# Rat_Clone_V1_0.net
KiCad netlist of a schematic drawn in EAGLE
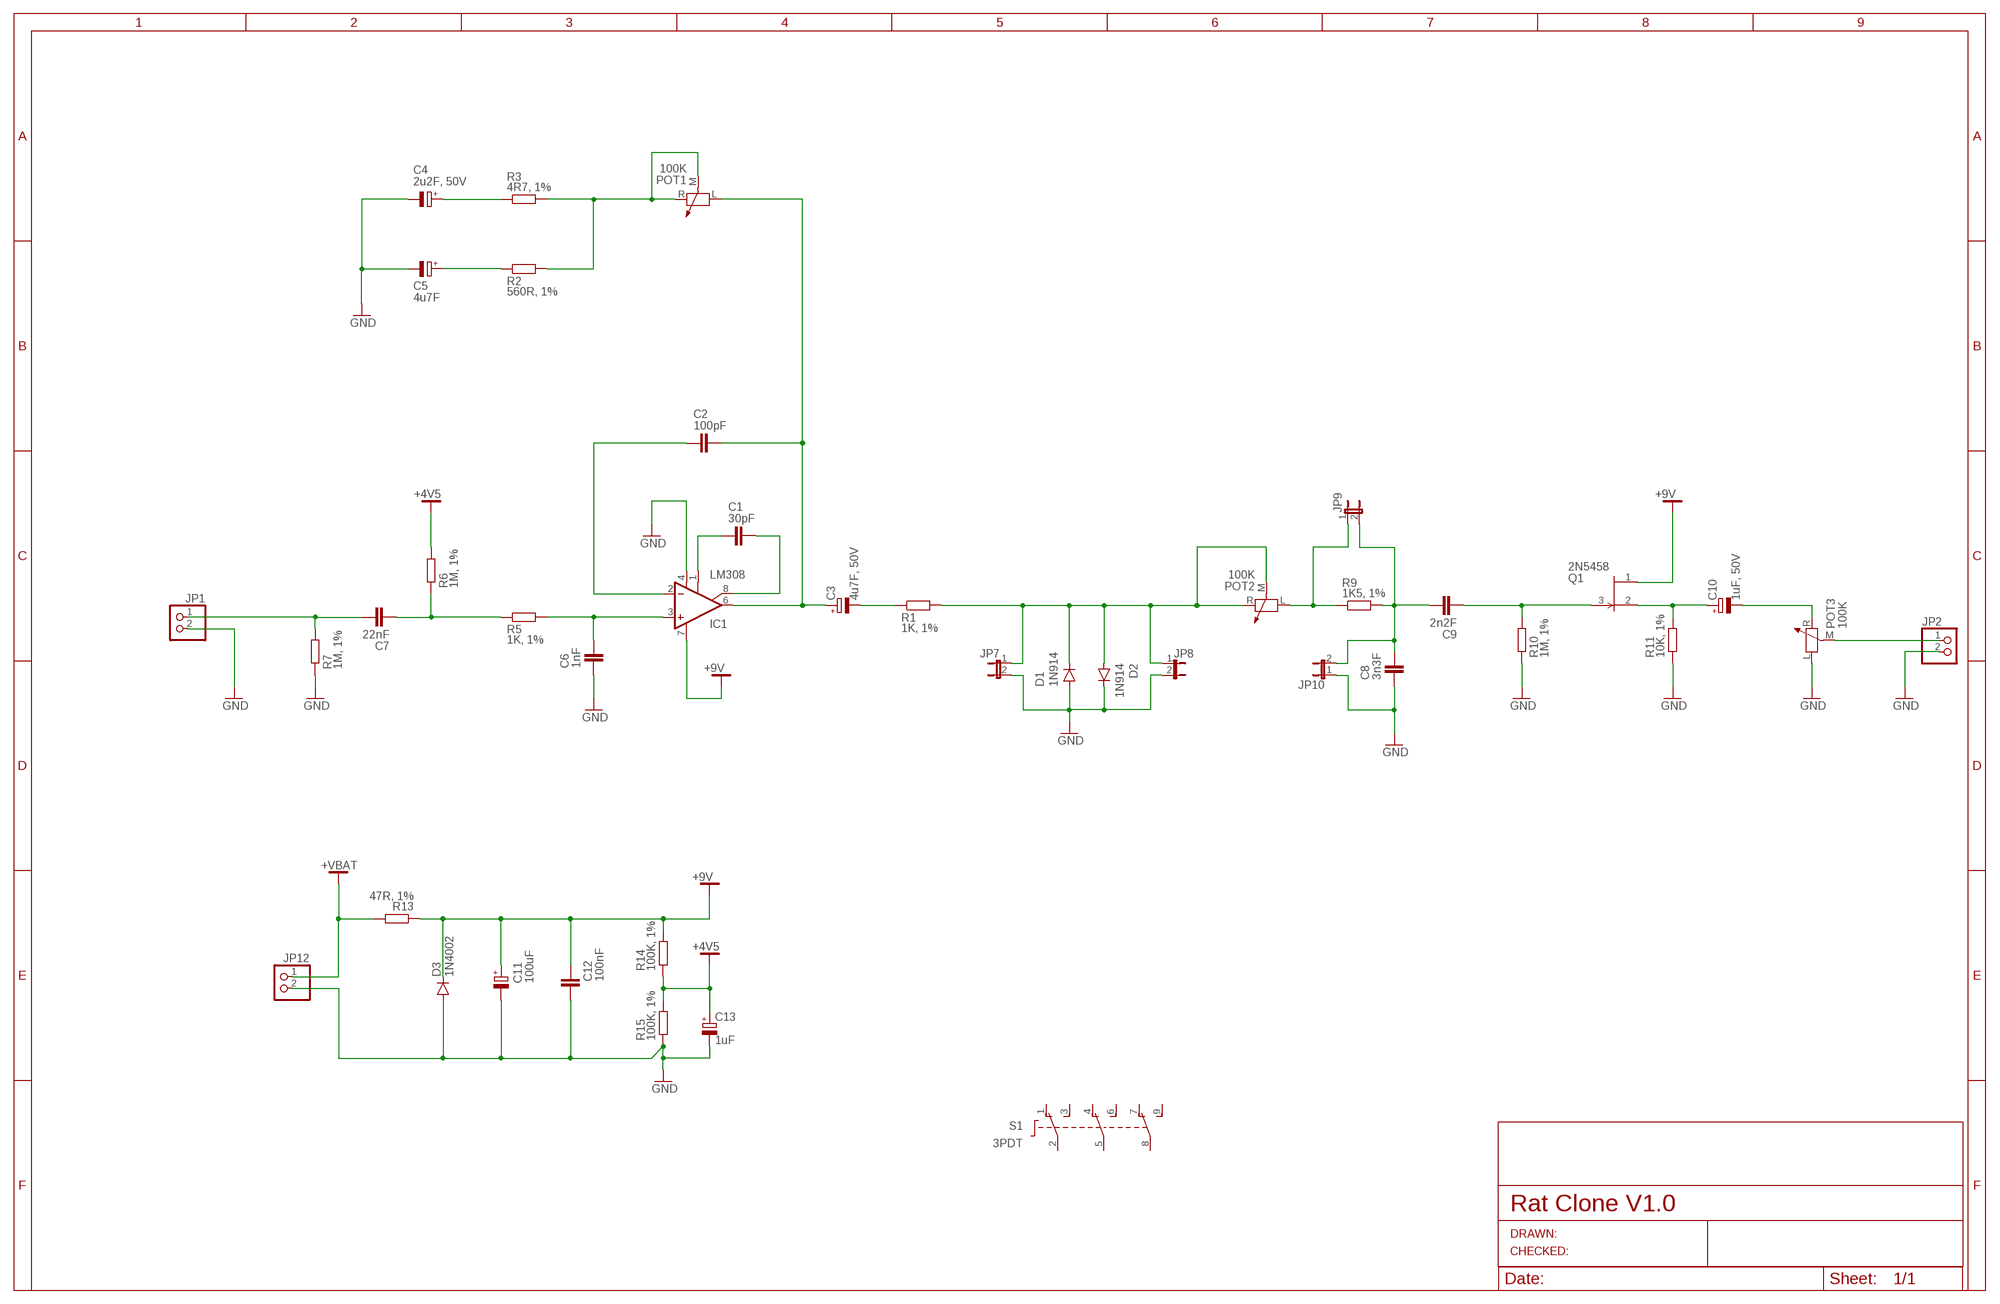
[diagram p0: schematic, sheet 1]

(export (version "E")
  (design (tool "Eeschema 10.0.6"))
  (components
    (comp (ref "C1")
      (value "30pF")
      (footprint "eagle-import:C025-025X050")
      (fields (field (name "MF") "KEMET ") (field (name "MPN") "C315C300J3G5TA"))
      (libsource (lib "eagle-import") (part "C-EU025-025X050"))
    )
    (comp (ref "C2")
      (value "100pF")
      (footprint "eagle-import:C025-025X050")
      (fields (field (name "MF") "Vishay / BC Components ") (field (name "MPN") "K101J15C0GF5TL2"))
      (libsource (lib "eagle-import") (part "C-EU025-025X050"))
    )
    (comp (ref "C3")
      (value "4u7F, 50V")
      (footprint "eagle-import:E2,5-6")
      (fields (field (name "MF") "MULTICOMP PRO") (field (name "MPN") "MCGPR50V475M5X11"))
      (libsource (lib "eagle-import") (part "CPOL-EUE2.5-6"))
    )
    (comp (ref "C4")
      (value "2u2F, 50V")
      (footprint "eagle-import:E2,5-6")
      (fields (field (name "MF") "MULTICOMP PRO") (field (name "MPN") "MCMR50V225M4X7"))
      (libsource (lib "eagle-import") (part "CPOL-EUE2.5-6"))
    )
    (comp (ref "C5")
      (value "4u7F")
      (footprint "eagle-import:E2,5-6")
      (fields (field (name "MF") "MULTICOMP PRO") (field (name "MPN") "MCMR50V475M4X7"))
      (libsource (lib "eagle-import") (part "CPOL-EUE2.5-6"))
    )
    (comp (ref "C6")
      (value "1nF")
      (footprint "eagle-import:C025-025X050")
      (fields (field (name "MF") "KEMET") (field (name "MPN") "R82EC1100DQ50J"))
      (libsource (lib "eagle-import") (part "C-EU025-025X050"))
    )
    (comp (ref "C7")
      (value "22nF")
      (footprint "eagle-import:C050-025X075")
      (fields (field (name "MF") "KEMET") (field (name "MPN") "R82EC2220DQ50JB"))
      (libsource (lib "eagle-import") (part "C-EU050-025X075"))
    )
    (comp (ref "C8")
      (value "3n3F")
      (footprint "eagle-import:C025-025X050")
      (fields (field (name "MF") "kemet") (field (name "MPN") "R82EC1330DQ50JB"))
      (libsource (lib "eagle-import") (part "C-EU025-025X050"))
    )
    (comp (ref "C9")
      (value "2n2F")
      (footprint "eagle-import:C025-025X050")
      (fields (field (name "MF") "Faratronic") (field (name "MPN") "C242A222J20C450"))
      (libsource (lib "eagle-import") (part "C-EU025-025X050"))
    )
    (comp (ref "C10")
      (value "1uF, 50V")
      (footprint "eagle-import:E2,5-6")
      (fields (field (name "MF") "MULTICOMP PRO") (field (name "MPN") "MCGPR50V105M5X11"))
      (libsource (lib "eagle-import") (part "CPOL-EUE2.5-6"))
    )
    (comp (ref "C11")
      (value "100uF")
      (footprint "eagle-import:E2,5-5")
      (fields (field (name "MF") "KEMET ") (field (name "MPN") "ESK107M016AC3AA "))
      (libsource (lib "eagle-import") (part "CPOL-EUE2.5-5"))
    )
    (comp (ref "C12")
      (value "100nF")
      (footprint "eagle-import:C025-025X050")
      (fields (field (name "MF") "KEMET") (field (name "MPN") "R82EC3100DQ70JB"))
      (libsource (lib "eagle-import") (part "C-EU025-025X050"))
    )
    (comp (ref "C13")
      (value "1uF")
      (footprint "eagle-import:E2,5-6")
      (fields (field (name "MF") "MULTICOMP PRO") (field (name "MPN") "MCGPR50V105M5X11"))
      (libsource (lib "eagle-import") (part "CPOL-EUE2.5-6"))
    )
    (comp (ref "D1")
      (value "1N914")
      (footprint "eagle-import:DO35-10")
      (fields (field (name "MF") "Fairchild Semiconductor") (field (name "MPN") "1N914"))
      (libsource (lib "eagle-import") (part "1N4148DO35-10"))
    )
    (comp (ref "D2")
      (value "1N914")
      (footprint "eagle-import:DO35-10")
      (fields (field (name "MF") "Fairchild Semiconductor") (field (name "MPN") "1N914"))
      (libsource (lib "eagle-import") (part "1N4148DO35-10"))
    )
    (comp (ref "D3")
      (value "1N4002")
      (footprint "eagle-import:DO41-10")
      (fields (field (name "MF") "onsemi ") (field (name "MPN") "1N4002G "))
      (libsource (lib "eagle-import") (part "1N4004"))
    )
    (comp (ref "IC1")
      (value "LM308")
      (footprint "eagle-import:DIL08")
      (libsource (lib "eagle-import") (part "LM308N"))
    )
    (comp (ref "JP1")
      (value "PINHD-1X2")
      (footprint "eagle-import:1X02")
      (fields (field (name "MF") "TruConnect") (field (name "MPN") "20-0134"))
      (libsource (lib "eagle-import") (part "PINHD-1X2"))
    )
    (comp (ref "JP2")
      (value "PINHD-1X2")
      (footprint "eagle-import:1X02")
      (fields (field (name "MF") "TruConnect") (field (name "MPN") "20-0134"))
      (libsource (lib "eagle-import") (part "PINHD-1X2"))
    )
    (comp (ref "JP7")
      (value "JP1E")
      (footprint "eagle-import:JP1")
      (libsource (lib "eagle-import") (part "JP1E"))
    )
    (comp (ref "JP8")
      (value "JP1E")
      (footprint "eagle-import:JP1")
      (libsource (lib "eagle-import") (part "JP1E"))
    )
    (comp (ref "JP9")
      (value "JP1E")
      (footprint "eagle-import:JP1")
      (libsource (lib "eagle-import") (part "JP1E"))
    )
    (comp (ref "JP10")
      (value "JP1E")
      (footprint "eagle-import:JP1")
      (libsource (lib "eagle-import") (part "JP1E"))
    )
    (comp (ref "JP12")
      (value "PINHD-1X2")
      (footprint "eagle-import:1X02")
      (fields (field (name "MF") "TruConnect") (field (name "MPN") "20-0134"))
      (libsource (lib "eagle-import") (part "PINHD-1X2"))
    )
    (comp (ref "POT1")
      (value "100K")
      (footprint "eagle-import:MA03-1")
      (libsource (lib "eagle-import") (part "WIRED_POT"))
    )
    (comp (ref "POT2")
      (value "100K")
      (footprint "eagle-import:MA03-1")
      (libsource (lib "eagle-import") (part "WIRED_POT"))
    )
    (comp (ref "POT3")
      (value "100K")
      (footprint "eagle-import:MA03-1")
      (libsource (lib "eagle-import") (part "WIRED_POT"))
    )
    (comp (ref "Q1")
      (value "2N5458")
      (footprint "eagle-import:TO92-")
      (fields (field (name "MF") "Central Semiconductor ") (field (name "MPN") "2N5458 PBFREE"))
      (libsource (lib "eagle-import") (part "2N5458"))
    )
    (comp (ref "R1")
      (value "1K, 1%")
      (footprint "eagle-import:0207_7")
      (fields (field (name "MF") "Royal Ohm") (field (name "MPN") "MF0W4FF1001KIT"))
      (libsource (lib "eagle-import") (part "R-EU_0207/7"))
    )
    (comp (ref "R2")
      (value "560R, 1%")
      (footprint "eagle-import:0207_7")
      (fields (field (name "MF") "Royal Ohm") (field (name "MPN") "MFF04FF5600KIT"))
      (libsource (lib "eagle-import") (part "R-EU_0207/7"))
    )
    (comp (ref "R3")
      (value "4R7, 1%")
      (footprint "eagle-import:0207_7")
      (fields (field (name "MF") "Royal Ohm") (field (name "MPN") "MF0W4FF470KKIT"))
      (libsource (lib "eagle-import") (part "R-EU_0207/7"))
    )
    (comp (ref "R5")
      (value "1K, 1%")
      (footprint "eagle-import:0207_7")
      (fields (field (name "MF") "Royal Ohm") (field (name "MPN") "MF0W4FF1001KIT"))
      (libsource (lib "eagle-import") (part "R-EU_0207/7"))
    )
    (comp (ref "R6")
      (value "1M, 1%")
      (footprint "eagle-import:0207_7")
      (fields (field (name "MF") "Royal Ohm") (field (name "MPN") "MF0W4FF1004KIT"))
      (libsource (lib "eagle-import") (part "R-EU_0207/7"))
    )
    (comp (ref "R7")
      (value "1M, 1%")
      (footprint "eagle-import:0207_7")
      (fields (field (name "MF") "Royal Ohm") (field (name "MPN") "MF0W4FF1004KIT"))
      (libsource (lib "eagle-import") (part "R-EU_0207/7"))
    )
    (comp (ref "R9")
      (value "1K5, 1%")
      (footprint "eagle-import:0207_7")
      (fields (field (name "MF") "Royal Ohm") (field (name "MPN") "MF0W4FF1501KIT"))
      (libsource (lib "eagle-import") (part "R-EU_0207/7"))
    )
    (comp (ref "R10")
      (value "1M, 1%")
      (footprint "eagle-import:0207_7")
      (fields (field (name "MF") "Royal Ohm") (field (name "MPN") "MF0W4FF1004KIT"))
      (libsource (lib "eagle-import") (part "R-EU_0207/7"))
    )
    (comp (ref "R11")
      (value "10K, 1%")
      (footprint "eagle-import:0207_7")
      (fields (field (name "MF") "Royal Ohm") (field (name "MPN") "MF0W4FF1002KIT"))
      (libsource (lib "eagle-import") (part "R-EU_0207/7"))
    )
    (comp (ref "R13")
      (value "47R, 1%")
      (footprint "eagle-import:0207_7")
      (fields (field (name "MF") "Royal Ohm") (field (name "MPN") "MF006FF470JKIT"))
      (libsource (lib "eagle-import") (part "R-EU_0207/7"))
    )
    (comp (ref "R14")
      (value "100K, 1%")
      (footprint "eagle-import:0207_7")
      (fields (field (name "MF") "Royal Ohm") (field (name "MPN") "MF0W4FF1003KIT"))
      (libsource (lib "eagle-import") (part "R-EU_0207/7"))
    )
    (comp (ref "R15")
      (value "100K, 1%")
      (footprint "eagle-import:0207_7")
      (fields (field (name "MF") "Royal Ohm") (field (name "MPN") "MF0W4FF1003KIT"))
      (libsource (lib "eagle-import") (part "R-EU_0207/7"))
    )
    (comp (ref "S1")
      (value "3PDT")
      (footprint "eagle-import:3PDT")
      (fields (field (name "MF") "Taiwan Alpha") (field (name "MPN") "SF17020F-0302-21R-L"))
      (libsource (lib "eagle-import") (part "3PDT"))
    )
  )
  (nets
    (net (code "1") (name "+4V5") (class "Default")
      (node (ref "C13") (pin "+") (pinfunction "+_+") (pintype "passive"))
      (node (ref "R14") (pin "1") (pinfunction "1_1") (pintype "passive"))
      (node (ref "R15") (pin "2") (pinfunction "2_2") (pintype "passive"))
      (node (ref "R6") (pin "2") (pinfunction "2_2") (pintype "passive"))
    )
    (net (code "2") (name "+9V") (class "Default")
      (node (ref "C11") (pin "+") (pinfunction "+_+") (pintype "passive"))
      (node (ref "C12") (pin "1") (pinfunction "1_1") (pintype "passive"))
      (node (ref "D3") (pin "C") (pinfunction "C_C") (pintype "passive"))
      (node (ref "IC1") (pin "7") (pinfunction "V+_7") (pintype "power_in"))
      (node (ref "Q1") (pin "1") (pinfunction "D_1") (pintype "passive"))
      (node (ref "R13") (pin "1") (pinfunction "1_1") (pintype "passive"))
      (node (ref "R14") (pin "2") (pinfunction "2_2") (pintype "passive"))
    )
    (net (code "3") (name "+VBAT") (class "Default")
      (node (ref "JP12") (pin "1") (pinfunction "1_1") (pintype "passive"))
      (node (ref "R13") (pin "2") (pinfunction "2_2") (pintype "passive"))
    )
    (net (code "4") (name "GND") (class "Default")
      (node (ref "C11") (pin "-") (pinfunction "-_-") (pintype "passive"))
      (node (ref "C12") (pin "2") (pinfunction "2_2") (pintype "passive"))
      (node (ref "C13") (pin "-") (pinfunction "-_-") (pintype "passive"))
      (node (ref "C4") (pin "-") (pinfunction "-_-") (pintype "passive"))
      (node (ref "C5") (pin "-") (pinfunction "-_-") (pintype "passive"))
      (node (ref "C6") (pin "1") (pinfunction "1_1") (pintype "passive"))
      (node (ref "C8") (pin "1") (pinfunction "1_1") (pintype "passive"))
      (node (ref "D1") (pin "A") (pinfunction "A_A") (pintype "passive"))
      (node (ref "D2") (pin "C") (pinfunction "C_C") (pintype "passive"))
      (node (ref "D3") (pin "A") (pinfunction "A_A") (pintype "passive"))
      (node (ref "IC1") (pin "4") (pinfunction "V-_4") (pintype "power_in"))
      (node (ref "JP1") (pin "2") (pinfunction "2_2") (pintype "passive"))
      (node (ref "JP10") (pin "1") (pinfunction "1_1") (pintype "passive"))
      (node (ref "JP12") (pin "2") (pinfunction "2_2") (pintype "passive"))
      (node (ref "JP2") (pin "2") (pinfunction "2_2") (pintype "passive"))
      (node (ref "JP7") (pin "2") (pinfunction "2_2") (pintype "passive"))
      (node (ref "JP8") (pin "2") (pinfunction "2_2") (pintype "passive"))
      (node (ref "POT3") (pin "L") (pinfunction "1_L") (pintype "passive"))
      (node (ref "R10") (pin "1") (pinfunction "1_1") (pintype "passive"))
      (node (ref "R11") (pin "1") (pinfunction "1_1") (pintype "passive"))
      (node (ref "R15") (pin "1") (pinfunction "1_1") (pintype "passive"))
      (node (ref "R7") (pin "1") (pinfunction "1_1") (pintype "passive"))
    )
    (net (code "5") (name "Net-(C3-Pad-)") (class "Default")
      (node (ref "C3") (pin "-") (pinfunction "-_-") (pintype "passive"))
      (node (ref "R1") (pin "1") (pinfunction "1_1") (pintype "passive"))
    )
    (net (code "6") (name "Net-(C4-Pad+)") (class "Default")
      (node (ref "C4") (pin "+") (pinfunction "+_+") (pintype "passive"))
      (node (ref "R3") (pin "1") (pinfunction "1_1") (pintype "passive"))
    )
    (net (code "7") (name "Net-(C5-Pad+)") (class "Default")
      (node (ref "C5") (pin "+") (pinfunction "+_+") (pintype "passive"))
      (node (ref "R2") (pin "1") (pinfunction "1_1") (pintype "passive"))
    )
    (net (code "8") (name "Net-(C7-Pad1)") (class "Default")
      (node (ref "C7") (pin "1") (pinfunction "1_1") (pintype "passive"))
      (node (ref "R5") (pin "1") (pinfunction "1_1") (pintype "passive"))
      (node (ref "R6") (pin "1") (pinfunction "1_1") (pintype "passive"))
    )
    (net (code "9") (name "Net-(C7-Pad2)") (class "Default")
      (node (ref "C7") (pin "2") (pinfunction "2_2") (pintype "passive"))
      (node (ref "JP1") (pin "1") (pinfunction "1_1") (pintype "passive"))
      (node (ref "R7") (pin "2") (pinfunction "2_2") (pintype "passive"))
    )
    (net (code "10") (name "Net-(C8-Pad2)") (class "Default")
      (node (ref "C8") (pin "2") (pinfunction "2_2") (pintype "passive"))
      (node (ref "C9") (pin "2") (pinfunction "2_2") (pintype "passive"))
      (node (ref "JP10") (pin "2") (pinfunction "2_2") (pintype "passive"))
      (node (ref "JP9") (pin "2") (pinfunction "2_2") (pintype "passive"))
      (node (ref "R9") (pin "2") (pinfunction "2_2") (pintype "passive"))
    )
    (net (code "11") (name "Net-(IC1-+IN)") (class "Default")
      (node (ref "C6") (pin "2") (pinfunction "2_2") (pintype "passive"))
      (node (ref "IC1") (pin "3") (pinfunction "+IN_3") (pintype "input"))
      (node (ref "R5") (pin "2") (pinfunction "2_2") (pintype "passive"))
    )
    (net (code "12") (name "Net-(IC1--IN)") (class "Default")
      (node (ref "C2") (pin "1") (pinfunction "1_1") (pintype "passive"))
      (node (ref "IC1") (pin "2") (pinfunction "-IN_2") (pintype "input"))
    )
    (net (code "13") (name "Net-(IC1-CMP1)") (class "Default")
      (node (ref "C1") (pin "1") (pinfunction "1_1") (pintype "passive"))
      (node (ref "IC1") (pin "1") (pinfunction "CMP1_1") (pintype "passive"))
    )
    (net (code "14") (name "Net-(IC1-CMP2)") (class "Default")
      (node (ref "C1") (pin "2") (pinfunction "2_2") (pintype "passive"))
      (node (ref "IC1") (pin "8") (pinfunction "CMP2_8") (pintype "passive"))
    )
    (net (code "15") (name "Net-(IC1-OUT)") (class "Default")
      (node (ref "C2") (pin "2") (pinfunction "2_2") (pintype "passive"))
      (node (ref "C3") (pin "+") (pinfunction "+_+") (pintype "passive"))
      (node (ref "IC1") (pin "6") (pinfunction "OUT_6") (pintype "output"))
      (node (ref "POT1") (pin "L") (pinfunction "1_L") (pintype "passive"))
    )
    (net (code "16") (name "Net-(POT1-2)") (class "Default")
      (node (ref "POT1") (pin "M") (pinfunction "3_M") (pintype "passive"))
      (node (ref "POT1") (pin "R") (pinfunction "2_R") (pintype "passive"))
      (node (ref "R2") (pin "2") (pinfunction "2_2") (pintype "passive"))
      (node (ref "R3") (pin "2") (pinfunction "2_2") (pintype "passive"))
    )
    (net (code "17") (name "Net-(POT2-1)") (class "Default")
      (node (ref "JP9") (pin "1") (pinfunction "1_1") (pintype "passive"))
      (node (ref "POT2") (pin "L") (pinfunction "1_L") (pintype "passive"))
      (node (ref "R9") (pin "1") (pinfunction "1_1") (pintype "passive"))
    )
    (net (code "18") (name "Net-(POT2-2)") (class "Default")
      (node (ref "D1") (pin "C") (pinfunction "C_C") (pintype "passive"))
      (node (ref "D2") (pin "A") (pinfunction "A_A") (pintype "passive"))
      (node (ref "JP7") (pin "1") (pinfunction "1_1") (pintype "passive"))
      (node (ref "JP8") (pin "1") (pinfunction "1_1") (pintype "passive"))
      (node (ref "POT2") (pin "M") (pinfunction "3_M") (pintype "passive"))
      (node (ref "POT2") (pin "R") (pinfunction "2_R") (pintype "passive"))
      (node (ref "R1") (pin "2") (pinfunction "2_2") (pintype "passive"))
    )
    (net (code "19") (name "Net-(POT3-2)") (class "Default")
      (node (ref "C10") (pin "-") (pinfunction "-_-") (pintype "passive"))
      (node (ref "POT3") (pin "R") (pinfunction "2_R") (pintype "passive"))
    )
    (net (code "20") (name "Net-(POT3-3)") (class "Default")
      (node (ref "JP2") (pin "1") (pinfunction "1_1") (pintype "passive"))
      (node (ref "POT3") (pin "M") (pinfunction "3_M") (pintype "passive"))
    )
    (net (code "21") (name "Net-(Q1-G)") (class "Default")
      (node (ref "C9") (pin "1") (pinfunction "1_1") (pintype "passive"))
      (node (ref "Q1") (pin "3") (pinfunction "G_3") (pintype "passive"))
      (node (ref "R10") (pin "2") (pinfunction "2_2") (pintype "passive"))
    )
    (net (code "22") (name "Net-(Q1-S)") (class "Default")
      (node (ref "C10") (pin "+") (pinfunction "+_+") (pintype "passive"))
      (node (ref "Q1") (pin "2") (pinfunction "S_2") (pintype "passive"))
      (node (ref "R11") (pin "2") (pinfunction "2_2") (pintype "passive"))
    )
    (net (code "23") (name "unconnected-(S1-O1-Pad1)") (class "Default")
      (node (ref "S1") (pin "1") (pinfunction "O1_1") (pintype "passive"))
    )
    (net (code "24") (name "unconnected-(S1-O2-Pad4)") (class "Default")
      (node (ref "S1") (pin "4") (pinfunction "O2_4") (pintype "passive"))
    )
    (net (code "25") (name "unconnected-(S1-O3-Pad7)") (class "Default")
      (node (ref "S1") (pin "7") (pinfunction "O3_7") (pintype "passive"))
    )
    (net (code "26") (name "unconnected-(S1-P1-Pad2)") (class "Default")
      (node (ref "S1") (pin "2") (pinfunction "P1_2") (pintype "passive"))
    )
    (net (code "27") (name "unconnected-(S1-P2-Pad5)") (class "Default")
      (node (ref "S1") (pin "5") (pinfunction "P2_5") (pintype "passive"))
    )
    (net (code "28") (name "unconnected-(S1-P3-Pad8)") (class "Default")
      (node (ref "S1") (pin "8") (pinfunction "P3_8") (pintype "passive"))
    )
    (net (code "29") (name "unconnected-(S1-S1-Pad3)") (class "Default")
      (node (ref "S1") (pin "3") (pinfunction "S1_3") (pintype "passive"))
    )
    (net (code "30") (name "unconnected-(S1-S2-Pad6)") (class "Default")
      (node (ref "S1") (pin "6") (pinfunction "S2_6") (pintype "passive"))
    )
    (net (code "31") (name "unconnected-(S1-S3-Pad9)") (class "Default")
      (node (ref "S1") (pin "9") (pinfunction "S3_9") (pintype "passive"))
    )
  )
)
